# biggity.net
KiCad netlist of a schematic drawn in EAGLE
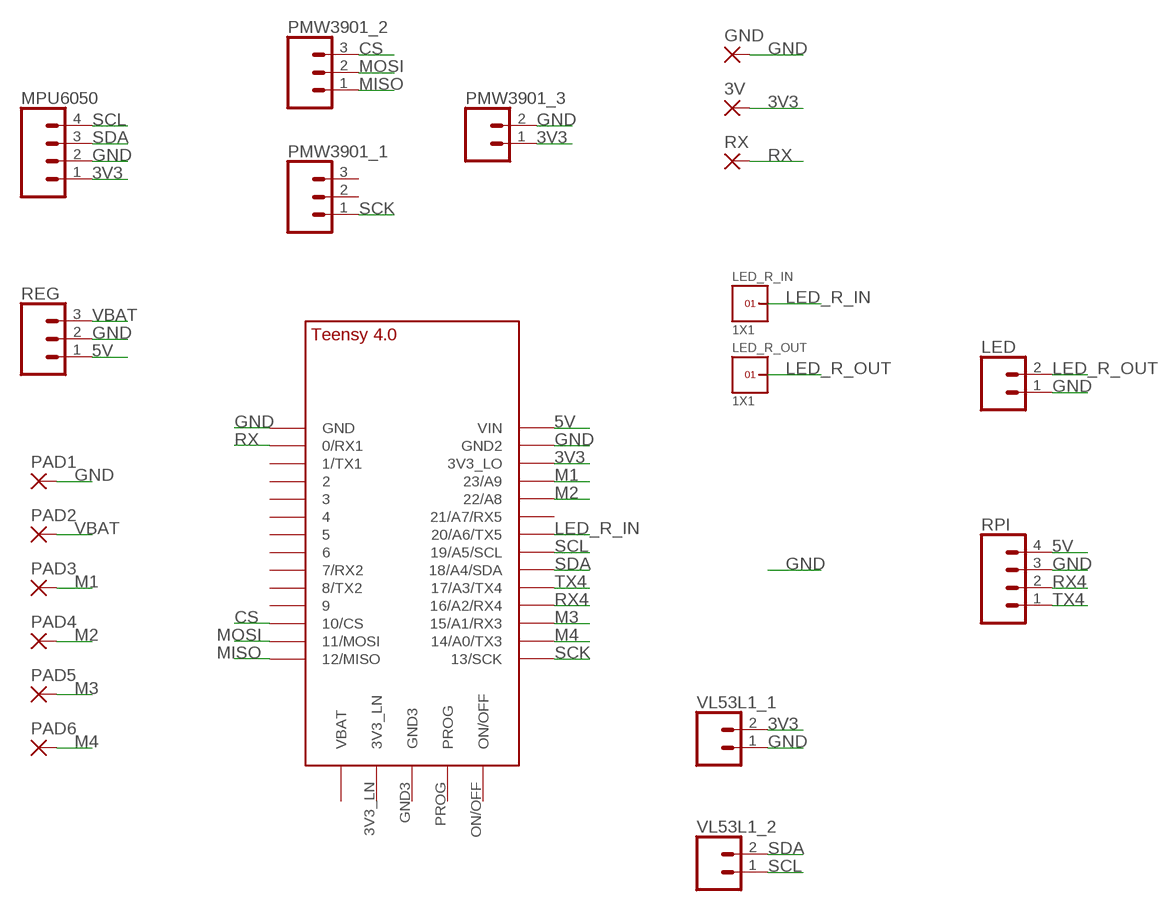
[diagram p0: schematic, sheet 1]

(export (version "E")
  (design (tool "Eeschema 10.0.6"))
  (components
    (comp (ref "3V")
      (value "SMD2")
      (footprint "eagle-import:SMD1,27-2,54")
      (libsource (lib "eagle-import") (part "SMD2"))
    )
    (comp (ref "GND")
      (value "SMD2")
      (footprint "eagle-import:SMD1,27-2,54")
      (libsource (lib "eagle-import") (part "SMD2"))
    )
    (comp (ref "LED")
      (value "CONN_021X02_NO_SILK")
      (footprint "eagle-import:1X02_NO_SILK")
      (libsource (lib "eagle-import") (part "CONN_021X02_NO_SILK"))
    )
    (comp (ref "LED_R_IN")
      (value "1X1")
      (footprint "eagle-import:1X1")
      (libsource (lib "eagle-import") (part "1X1"))
    )
    (comp (ref "LED_R_OUT")
      (value "1X1")
      (footprint "eagle-import:1X1")
      (libsource (lib "eagle-import") (part "1X1"))
    )
    (comp (ref "MPU6050")
      (value "CONN_041X04_NO_SILK")
      (footprint "eagle-import:1X04_NO_SILK")
      (libsource (lib "eagle-import") (part "CONN_041X04_NO_SILK"))
    )
    (comp (ref "PAD1")
      (value "SMD2")
      (footprint "eagle-import:SMD1,27-2,54")
      (libsource (lib "eagle-import") (part "SMD2"))
    )
    (comp (ref "PAD2")
      (value "SMD2")
      (footprint "eagle-import:SMD1,27-2,54")
      (libsource (lib "eagle-import") (part "SMD2"))
    )
    (comp (ref "PAD3")
      (value "SMD2")
      (footprint "eagle-import:SMD1,27-2,54")
      (libsource (lib "eagle-import") (part "SMD2"))
    )
    (comp (ref "PAD4")
      (value "SMD2")
      (footprint "eagle-import:SMD1,27-2,54")
      (libsource (lib "eagle-import") (part "SMD2"))
    )
    (comp (ref "PAD5")
      (value "SMD2")
      (footprint "eagle-import:SMD1,27-2,54")
      (libsource (lib "eagle-import") (part "SMD2"))
    )
    (comp (ref "PAD6")
      (value "SMD2")
      (footprint "eagle-import:SMD1,27-2,54")
      (libsource (lib "eagle-import") (part "SMD2"))
    )
    (comp (ref "PMW3901_1")
      (value "CONN_031X03_NO_SILK")
      (footprint "eagle-import:1X03_NO_SILK")
      (libsource (lib "eagle-import") (part "CONN_031X03_NO_SILK"))
    )
    (comp (ref "PMW3901_2")
      (value "CONN_031X03_NO_SILK")
      (footprint "eagle-import:1X03_NO_SILK")
      (libsource (lib "eagle-import") (part "CONN_031X03_NO_SILK"))
    )
    (comp (ref "PMW3901_3")
      (value "CONN_021X02_NO_SILK")
      (footprint "eagle-import:1X02_NO_SILK")
      (libsource (lib "eagle-import") (part "CONN_021X02_NO_SILK"))
    )
    (comp (ref "REG")
      (value "CONN_031X03_NO_SILK")
      (footprint "eagle-import:1X03_NO_SILK")
      (libsource (lib "eagle-import") (part "CONN_031X03_NO_SILK"))
    )
    (comp (ref "RPI")
      (value "CONN_041X04_NO_SILK")
      (footprint "eagle-import:1X04_NO_SILK")
      (libsource (lib "eagle-import") (part "CONN_041X04_NO_SILK"))
    )
    (comp (ref "RX")
      (value "SMD2")
      (footprint "eagle-import:SMD1,27-2,54")
      (libsource (lib "eagle-import") (part "SMD2"))
    )
    (comp (ref "U$1")
      (value "TEENSY_4.0")
      (footprint "eagle-import:TEENSY_4.0")
      (libsource (lib "eagle-import") (part "TEENSY_4.0"))
    )
    (comp (ref "VL53L1_1")
      (value "CONN_021X02_NO_SILK")
      (footprint "eagle-import:1X02_NO_SILK")
      (libsource (lib "eagle-import") (part "CONN_021X02_NO_SILK"))
    )
    (comp (ref "VL53L1_2")
      (value "CONN_021X02_NO_SILK")
      (footprint "eagle-import:1X02_NO_SILK")
      (libsource (lib "eagle-import") (part "CONN_021X02_NO_SILK"))
    )
  )
  (nets
    (net (code "1") (name "/3V3") (class "Default")
      (node (ref "3V") (pin "1") (pinfunction "P_1") (pintype "passive"))
      (node (ref "MPU6050") (pin "1") (pinfunction "1_1") (pintype "passive"))
      (node (ref "PMW3901_3") (pin "1") (pinfunction "1_1") (pintype "passive"))
      (node (ref "U$1") (pin "3V3_LO") (pinfunction "3V3_LO_3V3_LO") (pintype "bidirectional"))
      (node (ref "VL53L1_1") (pin "2") (pinfunction "2_2") (pintype "passive"))
    )
    (net (code "2") (name "/5V") (class "Default")
      (node (ref "REG") (pin "1") (pinfunction "1_1") (pintype "passive"))
      (node (ref "RPI") (pin "4") (pinfunction "4_4") (pintype "passive"))
      (node (ref "U$1") (pin "VIN") (pinfunction "VIN_VIN") (pintype "bidirectional"))
    )
    (net (code "3") (name "/CS") (class "Default")
      (node (ref "PMW3901_2") (pin "3") (pinfunction "3_3") (pintype "passive"))
      (node (ref "U$1") (pin "10/CS") (pinfunction "10/CS_10/CS") (pintype "bidirectional"))
    )
    (net (code "4") (name "/GND") (class "Default")
      (node (ref "GND") (pin "1") (pinfunction "P_1") (pintype "passive"))
      (node (ref "LED") (pin "1") (pinfunction "1_1") (pintype "passive"))
      (node (ref "MPU6050") (pin "2") (pinfunction "2_2") (pintype "passive"))
      (node (ref "PAD1") (pin "1") (pinfunction "P_1") (pintype "passive"))
      (node (ref "PMW3901_3") (pin "2") (pinfunction "2_2") (pintype "passive"))
      (node (ref "REG") (pin "2") (pinfunction "2_2") (pintype "passive"))
      (node (ref "RPI") (pin "3") (pinfunction "3_3") (pintype "passive"))
      (node (ref "U$1") (pin "GND") (pinfunction "GND_GND") (pintype "bidirectional"))
      (node (ref "U$1") (pin "GND2") (pinfunction "GND2_GND2") (pintype "bidirectional"))
      (node (ref "VL53L1_1") (pin "1") (pinfunction "1_1") (pintype "passive"))
    )
    (net (code "5") (name "/LED_R_IN") (class "Default")
      (node (ref "LED_R_IN") (pin "1") (pinfunction "1_1") (pintype "bidirectional"))
      (node (ref "U$1") (pin "20/A6") (pinfunction "20/A6/TX5_20/A6") (pintype "bidirectional"))
    )
    (net (code "6") (name "/LED_R_OUT") (class "Default")
      (node (ref "LED") (pin "2") (pinfunction "2_2") (pintype "passive"))
      (node (ref "LED_R_OUT") (pin "1") (pinfunction "1_1") (pintype "bidirectional"))
    )
    (net (code "7") (name "/M1") (class "Default")
      (node (ref "PAD3") (pin "1") (pinfunction "P_1") (pintype "passive"))
      (node (ref "U$1") (pin "23/A9") (pinfunction "23/A9_23/A9") (pintype "bidirectional"))
    )
    (net (code "8") (name "/M2") (class "Default")
      (node (ref "PAD4") (pin "1") (pinfunction "P_1") (pintype "passive"))
      (node (ref "U$1") (pin "22/A8") (pinfunction "22/A8_22/A8") (pintype "bidirectional"))
    )
    (net (code "9") (name "/M3") (class "Default")
      (node (ref "PAD5") (pin "1") (pinfunction "P_1") (pintype "passive"))
      (node (ref "U$1") (pin "15/A1") (pinfunction "15/A1/RX3_15/A1") (pintype "bidirectional"))
    )
    (net (code "10") (name "/M4") (class "Default")
      (node (ref "PAD6") (pin "1") (pinfunction "P_1") (pintype "passive"))
      (node (ref "U$1") (pin "14/A0") (pinfunction "14/A0/TX3_14/A0") (pintype "bidirectional"))
    )
    (net (code "11") (name "/MISO") (class "Default")
      (node (ref "PMW3901_2") (pin "1") (pinfunction "1_1") (pintype "passive"))
      (node (ref "U$1") (pin "12/MISO") (pinfunction "12/MISO_12/MISO") (pintype "bidirectional"))
    )
    (net (code "12") (name "/MOSI") (class "Default")
      (node (ref "PMW3901_2") (pin "2") (pinfunction "2_2") (pintype "passive"))
      (node (ref "U$1") (pin "11/MOSI") (pinfunction "11/MOSI_11/MOSI") (pintype "bidirectional"))
    )
    (net (code "13") (name "/RX") (class "Default")
      (node (ref "RX") (pin "1") (pinfunction "P_1") (pintype "passive"))
      (node (ref "U$1") (pin "0/RX") (pinfunction "0/RX1_0/RX") (pintype "bidirectional"))
    )
    (net (code "14") (name "/RX4") (class "Default")
      (node (ref "RPI") (pin "2") (pinfunction "2_2") (pintype "passive"))
      (node (ref "U$1") (pin "16/A2") (pinfunction "16/A2/RX4_16/A2") (pintype "bidirectional"))
    )
    (net (code "15") (name "/SCK") (class "Default")
      (node (ref "PMW3901_1") (pin "1") (pinfunction "1_1") (pintype "passive"))
      (node (ref "U$1") (pin "13/SCK") (pinfunction "13/SCK_13/SCK") (pintype "bidirectional"))
    )
    (net (code "16") (name "/SCL") (class "Default")
      (node (ref "MPU6050") (pin "4") (pinfunction "4_4") (pintype "passive"))
      (node (ref "U$1") (pin "19/A5/SCL") (pinfunction "19/A5/SCL_19/A5/SCL") (pintype "bidirectional"))
      (node (ref "VL53L1_2") (pin "1") (pinfunction "1_1") (pintype "passive"))
    )
    (net (code "17") (name "/SDA") (class "Default")
      (node (ref "MPU6050") (pin "3") (pinfunction "3_3") (pintype "passive"))
      (node (ref "U$1") (pin "18/A4/SDA") (pinfunction "18/A4/SDA_18/A4/SDA") (pintype "bidirectional"))
      (node (ref "VL53L1_2") (pin "2") (pinfunction "2_2") (pintype "passive"))
    )
    (net (code "18") (name "/TX4") (class "Default")
      (node (ref "RPI") (pin "1") (pinfunction "1_1") (pintype "passive"))
      (node (ref "U$1") (pin "17/A3") (pinfunction "17/A3/TX4_17/A3") (pintype "bidirectional"))
    )
    (net (code "19") (name "/VBAT") (class "Default")
      (node (ref "PAD2") (pin "1") (pinfunction "P_1") (pintype "passive"))
      (node (ref "REG") (pin "3") (pinfunction "3_3") (pintype "passive"))
    )
    (net (code "20") (name "unconnected-(PMW3901_1-Pad2)") (class "Default")
      (node (ref "PMW3901_1") (pin "2") (pinfunction "2_2") (pintype "passive"))
    )
    (net (code "21") (name "unconnected-(PMW3901_1-Pad3)") (class "Default")
      (node (ref "PMW3901_1") (pin "3") (pinfunction "3_3") (pintype "passive"))
    )
    (net (code "22") (name "unconnected-(U$1-1{slash}TX1-Pad1{slash}TX)") (class "Default")
      (node (ref "U$1") (pin "1/TX") (pinfunction "1/TX1_1/TX") (pintype "bidirectional"))
    )
    (net (code "23") (name "unconnected-(U$1-3-Pad3{slash}CANTX)") (class "Default")
      (node (ref "U$1") (pin "3/CANTX") (pinfunction "3_3/CANTX") (pintype "bidirectional"))
    )
    (net (code "24") (name "unconnected-(U$1-4-Pad4{slash}CANRX)") (class "Default")
      (node (ref "U$1") (pin "4/CANRX") (pinfunction "4_4/CANRX") (pintype "bidirectional"))
    )
    (net (code "25") (name "unconnected-(U$1-7{slash}RX2-Pad7)") (class "Default")
      (node (ref "U$1") (pin "7") (pinfunction "7/RX2_7") (pintype "bidirectional"))
    )
    (net (code "26") (name "unconnected-(U$1-8{slash}TX2-Pad8)") (class "Default")
      (node (ref "U$1") (pin "8") (pinfunction "8/TX2_8") (pintype "bidirectional"))
    )
    (net (code "27") (name "unconnected-(U$1-9-Pad9{slash}CS)") (class "Default")
      (node (ref "U$1") (pin "9/CS") (pinfunction "9_9/CS") (pintype "bidirectional"))
    )
    (net (code "28") (name "unconnected-(U$1-21{slash}A7{slash}RX5-Pad21{slash}A7)") (class "Default")
      (node (ref "U$1") (pin "21/A7") (pinfunction "21/A7/RX5_21/A7") (pintype "bidirectional"))
    )
    (net (code "29") (name "unconnected-(U$1-Pad2)") (class "Default")
      (node (ref "U$1") (pin "2") (pinfunction "2_2") (pintype "bidirectional"))
    )
    (net (code "30") (name "unconnected-(U$1-Pad3V3_LN)") (class "Default")
      (node (ref "U$1") (pin "3V3_LN") (pinfunction "3V3_LN_3V3_LN") (pintype "bidirectional"))
    )
    (net (code "31") (name "unconnected-(U$1-Pad5)") (class "Default")
      (node (ref "U$1") (pin "5") (pinfunction "5_5") (pintype "bidirectional"))
    )
    (net (code "32") (name "unconnected-(U$1-Pad6)") (class "Default")
      (node (ref "U$1") (pin "6") (pinfunction "6_6") (pintype "bidirectional"))
    )
    (net (code "33") (name "unconnected-(U$1-PadGND3)") (class "Default")
      (node (ref "U$1") (pin "GND3") (pinfunction "GND3_GND3") (pintype "bidirectional"))
    )
    (net (code "34") (name "unconnected-(U$1-PadON{slash}OFF)") (class "Default")
      (node (ref "U$1") (pin "ON/OFF") (pinfunction "ON/OFF_ON/OFF") (pintype "bidirectional"))
    )
    (net (code "35") (name "unconnected-(U$1-PadPROG)") (class "Default")
      (node (ref "U$1") (pin "PROG") (pinfunction "PROG_PROG") (pintype "bidirectional"))
    )
    (net (code "36") (name "unconnected-(U$1-VBAT-PadVBAT\\)") (class "Default")
      (node (ref "U$1") (pin "VBAT\\") (pinfunction "VBAT_VBAT\\") (pintype "bidirectional"))
    )
  )
)
